# v0.net
KiCad netlist of a schematic drawn in EAGLE
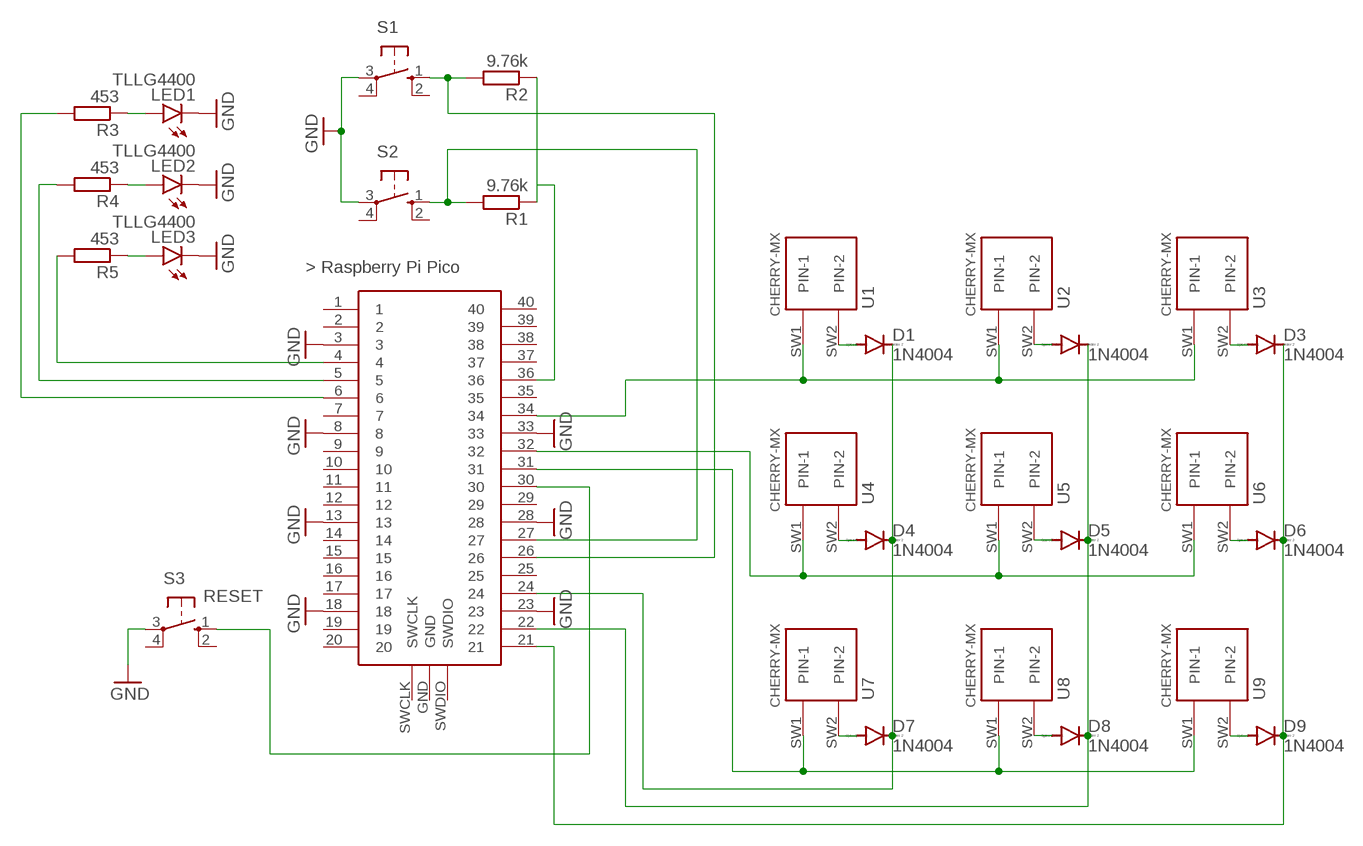
[diagram p0: schematic, sheet 1]

(export (version "E")
  (design (tool "Eeschema 10.0.6"))
  (components
    (comp (ref "D1")
      (value "1N4004")
      (footprint "eagle-import:DO41-10")
      (libsource (lib "eagle-import") (part "1N4004"))
    )
    (comp (ref "D2")
      (value "1N4004")
      (footprint "eagle-import:DO41-10")
      (libsource (lib "eagle-import") (part "1N4004"))
    )
    (comp (ref "D3")
      (value "1N4004")
      (footprint "eagle-import:DO41-10")
      (libsource (lib "eagle-import") (part "1N4004"))
    )
    (comp (ref "D4")
      (value "1N4004")
      (footprint "eagle-import:DO41-10")
      (libsource (lib "eagle-import") (part "1N4004"))
    )
    (comp (ref "D5")
      (value "1N4004")
      (footprint "eagle-import:DO41-10")
      (libsource (lib "eagle-import") (part "1N4004"))
    )
    (comp (ref "D6")
      (value "1N4004")
      (footprint "eagle-import:DO41-10")
      (libsource (lib "eagle-import") (part "1N4004"))
    )
    (comp (ref "D7")
      (value "1N4004")
      (footprint "eagle-import:DO41-10")
      (libsource (lib "eagle-import") (part "1N4004"))
    )
    (comp (ref "D8")
      (value "1N4004")
      (footprint "eagle-import:DO41-10")
      (libsource (lib "eagle-import") (part "1N4004"))
    )
    (comp (ref "D9")
      (value "1N4004")
      (footprint "eagle-import:DO41-10")
      (libsource (lib "eagle-import") (part "1N4004"))
    )
    (comp (ref "LED1")
      (value "TLLG4400")
      (footprint "eagle-import:LED3MM")
      (fields (field (name "MF") "VISHAY SEMICONDUCTOR"))
      (libsource (lib "eagle-import") (part "TLLG4400"))
    )
    (comp (ref "LED2")
      (value "TLLG4400")
      (footprint "eagle-import:LED3MM")
      (fields (field (name "MF") "VISHAY SEMICONDUCTOR"))
      (libsource (lib "eagle-import") (part "TLLG4400"))
    )
    (comp (ref "LED3")
      (value "TLLG4400")
      (footprint "eagle-import:LED3MM")
      (fields (field (name "MF") "VISHAY SEMICONDUCTOR"))
      (libsource (lib "eagle-import") (part "TLLG4400"))
    )
    (comp (ref "R1")
      (value "9.76k")
      (footprint "eagle-import:VMTA55")
      (libsource (lib "eagle-import") (part "R-EU_VMTA55"))
    )
    (comp (ref "R2")
      (value "9.76k")
      (footprint "eagle-import:VMTA55")
      (libsource (lib "eagle-import") (part "R-EU_VMTA55"))
    )
    (comp (ref "R3")
      (value "453")
      (footprint "eagle-import:VMTA55")
      (libsource (lib "eagle-import") (part "R-EU_VMTA55"))
    )
    (comp (ref "R4")
      (value "453")
      (footprint "eagle-import:VMTA55")
      (libsource (lib "eagle-import") (part "R-EU_VMTA55"))
    )
    (comp (ref "R5")
      (value "453")
      (footprint "eagle-import:VMTA55")
      (libsource (lib "eagle-import") (part "R-EU_VMTA55"))
    )
    (comp (ref "S1")
      (value "10-XX")
      (footprint "eagle-import:B3F-10XX")
      (fields (field (name "MPN") "B3F-1000"))
      (libsource (lib "eagle-import") (part "10-XX"))
    )
    (comp (ref "S2")
      (value "10-XX")
      (footprint "eagle-import:B3F-10XX")
      (fields (field (name "MPN") "B3F-1000"))
      (libsource (lib "eagle-import") (part "10-XX"))
    )
    (comp (ref "S3")
      (value "RESET")
      (footprint "eagle-import:B3F-10XX")
      (fields (field (name "MPN") "B3F-1000"))
      (libsource (lib "eagle-import") (part "10-XX"))
    )
    (comp (ref "U$1")
      (value "RASPBERRY-PI-PICO_TH")
      (footprint "eagle-import:FT_RASPBERRY-PI-PICO_TH")
      (libsource (lib "eagle-import") (part "RASPBERRY-PI-PICO_TH"))
    )
    (comp (ref "U1")
      (value "CHERRY-MX")
      (footprint "eagle-import:CHERRY-MX")
      (libsource (lib "eagle-import") (part "CHERRY-MX"))
    )
    (comp (ref "U2")
      (value "CHERRY-MX")
      (footprint "eagle-import:CHERRY-MX")
      (libsource (lib "eagle-import") (part "CHERRY-MX"))
    )
    (comp (ref "U3")
      (value "CHERRY-MX")
      (footprint "eagle-import:CHERRY-MX")
      (libsource (lib "eagle-import") (part "CHERRY-MX"))
    )
    (comp (ref "U4")
      (value "CHERRY-MX")
      (footprint "eagle-import:CHERRY-MX")
      (libsource (lib "eagle-import") (part "CHERRY-MX"))
    )
    (comp (ref "U5")
      (value "CHERRY-MX")
      (footprint "eagle-import:CHERRY-MX")
      (libsource (lib "eagle-import") (part "CHERRY-MX"))
    )
    (comp (ref "U6")
      (value "CHERRY-MX")
      (footprint "eagle-import:CHERRY-MX")
      (libsource (lib "eagle-import") (part "CHERRY-MX"))
    )
    (comp (ref "U7")
      (value "CHERRY-MX")
      (footprint "eagle-import:CHERRY-MX")
      (libsource (lib "eagle-import") (part "CHERRY-MX"))
    )
    (comp (ref "U8")
      (value "CHERRY-MX")
      (footprint "eagle-import:CHERRY-MX")
      (libsource (lib "eagle-import") (part "CHERRY-MX"))
    )
    (comp (ref "U9")
      (value "CHERRY-MX")
      (footprint "eagle-import:CHERRY-MX")
      (libsource (lib "eagle-import") (part "CHERRY-MX"))
    )
  )
  (nets
    (net (code "1") (name "GND") (class "Default")
      (node (ref "LED1") (pin "K") (pinfunction "C_K") (pintype "passive"))
      (node (ref "LED2") (pin "K") (pinfunction "C_K") (pintype "passive"))
      (node (ref "LED3") (pin "K") (pinfunction "C_K") (pintype "passive"))
      (node (ref "S1") (pin "3") (pinfunction "P_3") (pintype "passive"))
      (node (ref "S2") (pin "3") (pinfunction "P_3") (pintype "passive"))
      (node (ref "S3") (pin "3") (pinfunction "P_3") (pintype "passive"))
      (node (ref "U$1") (pin "13") (pinfunction "13_13") (pintype "bidirectional"))
      (node (ref "U$1") (pin "18") (pinfunction "18_18") (pintype "bidirectional"))
      (node (ref "U$1") (pin "23") (pinfunction "23_23") (pintype "bidirectional"))
      (node (ref "U$1") (pin "28") (pinfunction "28_28") (pintype "bidirectional"))
      (node (ref "U$1") (pin "3") (pinfunction "3_3") (pintype "bidirectional"))
      (node (ref "U$1") (pin "33") (pinfunction "33_33") (pintype "bidirectional"))
      (node (ref "U$1") (pin "8") (pinfunction "8_8") (pintype "bidirectional"))
    )
    (net (code "2") (name "Net-(D1-PadC)") (class "Default")
      (node (ref "D1") (pin "C") (pinfunction "C_C") (pintype "passive"))
      (node (ref "D4") (pin "C") (pinfunction "C_C") (pintype "passive"))
      (node (ref "D7") (pin "C") (pinfunction "C_C") (pintype "passive"))
      (node (ref "U$1") (pin "24") (pinfunction "24_24") (pintype "bidirectional"))
    )
    (net (code "3") (name "Net-(D2-PadC)") (class "Default")
      (node (ref "D2") (pin "C") (pinfunction "C_C") (pintype "passive"))
      (node (ref "D5") (pin "C") (pinfunction "C_C") (pintype "passive"))
      (node (ref "D8") (pin "C") (pinfunction "C_C") (pintype "passive"))
      (node (ref "U$1") (pin "22") (pinfunction "22_22") (pintype "bidirectional"))
    )
    (net (code "4") (name "Net-(D3-PadC)") (class "Default")
      (node (ref "D3") (pin "C") (pinfunction "C_C") (pintype "passive"))
      (node (ref "D6") (pin "C") (pinfunction "C_C") (pintype "passive"))
      (node (ref "D9") (pin "C") (pinfunction "C_C") (pintype "passive"))
      (node (ref "U$1") (pin "21") (pinfunction "21_21") (pintype "bidirectional"))
    )
    (net (code "5") (name "Net-(LED1-PadA)") (class "Default")
      (node (ref "LED1") (pin "A") (pinfunction "A_A") (pintype "passive"))
      (node (ref "R3") (pin "1") (pinfunction "1_1") (pintype "passive"))
    )
    (net (code "6") (name "Net-(LED2-PadA)") (class "Default")
      (node (ref "LED2") (pin "A") (pinfunction "A_A") (pintype "passive"))
      (node (ref "R4") (pin "1") (pinfunction "1_1") (pintype "passive"))
    )
    (net (code "7") (name "Net-(LED3-PadA)") (class "Default")
      (node (ref "LED3") (pin "A") (pinfunction "A_A") (pintype "passive"))
      (node (ref "R5") (pin "1") (pinfunction "1_1") (pintype "passive"))
    )
    (net (code "8") (name "Net-(R1-Pad1)") (class "Default")
      (node (ref "R1") (pin "1") (pinfunction "1_1") (pintype "passive"))
      (node (ref "R2") (pin "1") (pinfunction "1_1") (pintype "passive"))
      (node (ref "U$1") (pin "36") (pinfunction "36_36") (pintype "bidirectional"))
    )
    (net (code "9") (name "Net-(R3-Pad2)") (class "Default")
      (node (ref "R3") (pin "2") (pinfunction "2_2") (pintype "passive"))
      (node (ref "U$1") (pin "6") (pinfunction "6_6") (pintype "bidirectional"))
    )
    (net (code "10") (name "Net-(R4-Pad2)") (class "Default")
      (node (ref "R4") (pin "2") (pinfunction "2_2") (pintype "passive"))
      (node (ref "U$1") (pin "5") (pinfunction "5_5") (pintype "bidirectional"))
    )
    (net (code "11") (name "Net-(R5-Pad2)") (class "Default")
      (node (ref "R5") (pin "2") (pinfunction "2_2") (pintype "passive"))
      (node (ref "U$1") (pin "4") (pinfunction "4_4") (pintype "bidirectional"))
    )
    (net (code "12") (name "Net-(S1-S)") (class "Default")
      (node (ref "R2") (pin "2") (pinfunction "2_2") (pintype "passive"))
      (node (ref "S1") (pin "1") (pinfunction "S_1") (pintype "passive"))
      (node (ref "U$1") (pin "26") (pinfunction "26_26") (pintype "bidirectional"))
    )
    (net (code "13") (name "Net-(S2-S)") (class "Default")
      (node (ref "R1") (pin "2") (pinfunction "2_2") (pintype "passive"))
      (node (ref "S2") (pin "1") (pinfunction "S_1") (pintype "passive"))
      (node (ref "U$1") (pin "27") (pinfunction "27_27") (pintype "bidirectional"))
    )
    (net (code "14") (name "Net-(S3-S)") (class "Default")
      (node (ref "S3") (pin "1") (pinfunction "S_1") (pintype "passive"))
      (node (ref "U$1") (pin "30") (pinfunction "30_30") (pintype "bidirectional"))
    )
    (net (code "15") (name "Net-(U1-PIN-1)") (class "Default")
      (node (ref "U$1") (pin "34") (pinfunction "34_34") (pintype "bidirectional"))
      (node (ref "U1") (pin "SW1") (pinfunction "PIN-1_SW1") (pintype "bidirectional"))
      (node (ref "U2") (pin "SW1") (pinfunction "PIN-1_SW1") (pintype "bidirectional"))
      (node (ref "U3") (pin "SW1") (pinfunction "PIN-1_SW1") (pintype "bidirectional"))
    )
    (net (code "16") (name "Net-(U1-PIN-2)") (class "Default")
      (node (ref "D1") (pin "A") (pinfunction "A_A") (pintype "passive"))
      (node (ref "U1") (pin "SW2") (pinfunction "PIN-2_SW2") (pintype "bidirectional"))
    )
    (net (code "17") (name "Net-(U2-PIN-2)") (class "Default")
      (node (ref "D2") (pin "A") (pinfunction "A_A") (pintype "passive"))
      (node (ref "U2") (pin "SW2") (pinfunction "PIN-2_SW2") (pintype "bidirectional"))
    )
    (net (code "18") (name "Net-(U3-PIN-2)") (class "Default")
      (node (ref "D3") (pin "A") (pinfunction "A_A") (pintype "passive"))
      (node (ref "U3") (pin "SW2") (pinfunction "PIN-2_SW2") (pintype "bidirectional"))
    )
    (net (code "19") (name "Net-(U4-PIN-1)") (class "Default")
      (node (ref "U$1") (pin "32") (pinfunction "32_32") (pintype "bidirectional"))
      (node (ref "U4") (pin "SW1") (pinfunction "PIN-1_SW1") (pintype "bidirectional"))
      (node (ref "U5") (pin "SW1") (pinfunction "PIN-1_SW1") (pintype "bidirectional"))
      (node (ref "U6") (pin "SW1") (pinfunction "PIN-1_SW1") (pintype "bidirectional"))
    )
    (net (code "20") (name "Net-(U4-PIN-2)") (class "Default")
      (node (ref "D4") (pin "A") (pinfunction "A_A") (pintype "passive"))
      (node (ref "U4") (pin "SW2") (pinfunction "PIN-2_SW2") (pintype "bidirectional"))
    )
    (net (code "21") (name "Net-(U5-PIN-2)") (class "Default")
      (node (ref "D5") (pin "A") (pinfunction "A_A") (pintype "passive"))
      (node (ref "U5") (pin "SW2") (pinfunction "PIN-2_SW2") (pintype "bidirectional"))
    )
    (net (code "22") (name "Net-(U6-PIN-2)") (class "Default")
      (node (ref "D6") (pin "A") (pinfunction "A_A") (pintype "passive"))
      (node (ref "U6") (pin "SW2") (pinfunction "PIN-2_SW2") (pintype "bidirectional"))
    )
    (net (code "23") (name "Net-(U7-PIN-1)") (class "Default")
      (node (ref "U$1") (pin "31") (pinfunction "31_31") (pintype "bidirectional"))
      (node (ref "U7") (pin "SW1") (pinfunction "PIN-1_SW1") (pintype "bidirectional"))
      (node (ref "U8") (pin "SW1") (pinfunction "PIN-1_SW1") (pintype "bidirectional"))
      (node (ref "U9") (pin "SW1") (pinfunction "PIN-1_SW1") (pintype "bidirectional"))
    )
    (net (code "24") (name "Net-(U7-PIN-2)") (class "Default")
      (node (ref "D7") (pin "A") (pinfunction "A_A") (pintype "passive"))
      (node (ref "U7") (pin "SW2") (pinfunction "PIN-2_SW2") (pintype "bidirectional"))
    )
    (net (code "25") (name "Net-(U8-PIN-2)") (class "Default")
      (node (ref "D8") (pin "A") (pinfunction "A_A") (pintype "passive"))
      (node (ref "U8") (pin "SW2") (pinfunction "PIN-2_SW2") (pintype "bidirectional"))
    )
    (net (code "26") (name "Net-(U9-PIN-2)") (class "Default")
      (node (ref "D9") (pin "A") (pinfunction "A_A") (pintype "passive"))
      (node (ref "U9") (pin "SW2") (pinfunction "PIN-2_SW2") (pintype "bidirectional"))
    )
    (net (code "27") (name "unconnected-(S1-P1-Pad4)") (class "Default")
      (node (ref "S1") (pin "4") (pinfunction "P1_4") (pintype "passive"))
    )
    (net (code "28") (name "unconnected-(S1-S1-Pad2)") (class "Default")
      (node (ref "S1") (pin "2") (pinfunction "S1_2") (pintype "passive"))
    )
    (net (code "29") (name "unconnected-(S2-P1-Pad4)") (class "Default")
      (node (ref "S2") (pin "4") (pinfunction "P1_4") (pintype "passive"))
    )
    (net (code "30") (name "unconnected-(S2-S1-Pad2)") (class "Default")
      (node (ref "S2") (pin "2") (pinfunction "S1_2") (pintype "passive"))
    )
    (net (code "31") (name "unconnected-(S3-P1-Pad4)") (class "Default")
      (node (ref "S3") (pin "4") (pinfunction "P1_4") (pintype "passive"))
    )
    (net (code "32") (name "unconnected-(S3-S1-Pad2)") (class "Default")
      (node (ref "S3") (pin "2") (pinfunction "S1_2") (pintype "passive"))
    )
    (net (code "33") (name "unconnected-(U$1-Pad1)") (class "Default")
      (node (ref "U$1") (pin "1") (pinfunction "1_1") (pintype "bidirectional"))
    )
    (net (code "34") (name "unconnected-(U$1-Pad2)") (class "Default")
      (node (ref "U$1") (pin "2") (pinfunction "2_2") (pintype "bidirectional"))
    )
    (net (code "35") (name "unconnected-(U$1-Pad7)") (class "Default")
      (node (ref "U$1") (pin "7") (pinfunction "7_7") (pintype "bidirectional"))
    )
    (net (code "36") (name "unconnected-(U$1-Pad9)") (class "Default")
      (node (ref "U$1") (pin "9") (pinfunction "9_9") (pintype "bidirectional"))
    )
    (net (code "37") (name "unconnected-(U$1-Pad10)") (class "Default")
      (node (ref "U$1") (pin "10") (pinfunction "10_10") (pintype "bidirectional"))
    )
    (net (code "38") (name "unconnected-(U$1-Pad11)") (class "Default")
      (node (ref "U$1") (pin "11") (pinfunction "11_11") (pintype "bidirectional"))
    )
    (net (code "39") (name "unconnected-(U$1-Pad12)") (class "Default")
      (node (ref "U$1") (pin "12") (pinfunction "12_12") (pintype "bidirectional"))
    )
    (net (code "40") (name "unconnected-(U$1-Pad14)") (class "Default")
      (node (ref "U$1") (pin "14") (pinfunction "14_14") (pintype "bidirectional"))
    )
    (net (code "41") (name "unconnected-(U$1-Pad15)") (class "Default")
      (node (ref "U$1") (pin "15") (pinfunction "15_15") (pintype "bidirectional"))
    )
    (net (code "42") (name "unconnected-(U$1-Pad16)") (class "Default")
      (node (ref "U$1") (pin "16") (pinfunction "16_16") (pintype "bidirectional"))
    )
    (net (code "43") (name "unconnected-(U$1-Pad17)") (class "Default")
      (node (ref "U$1") (pin "17") (pinfunction "17_17") (pintype "bidirectional"))
    )
    (net (code "44") (name "unconnected-(U$1-Pad19)") (class "Default")
      (node (ref "U$1") (pin "19") (pinfunction "19_19") (pintype "bidirectional"))
    )
    (net (code "45") (name "unconnected-(U$1-Pad20)") (class "Default")
      (node (ref "U$1") (pin "20") (pinfunction "20_20") (pintype "bidirectional"))
    )
    (net (code "46") (name "unconnected-(U$1-Pad25)") (class "Default")
      (node (ref "U$1") (pin "25") (pinfunction "25_25") (pintype "bidirectional"))
    )
    (net (code "47") (name "unconnected-(U$1-Pad29)") (class "Default")
      (node (ref "U$1") (pin "29") (pinfunction "29_29") (pintype "bidirectional"))
    )
    (net (code "48") (name "unconnected-(U$1-Pad35)") (class "Default")
      (node (ref "U$1") (pin "35") (pinfunction "35_35") (pintype "bidirectional"))
    )
    (net (code "49") (name "unconnected-(U$1-Pad37)") (class "Default")
      (node (ref "U$1") (pin "37") (pinfunction "37_37") (pintype "bidirectional"))
    )
    (net (code "50") (name "unconnected-(U$1-Pad38)") (class "Default")
      (node (ref "U$1") (pin "38") (pinfunction "38_38") (pintype "bidirectional"))
    )
    (net (code "51") (name "unconnected-(U$1-Pad39)") (class "Default")
      (node (ref "U$1") (pin "39") (pinfunction "39_39") (pintype "bidirectional"))
    )
    (net (code "52") (name "unconnected-(U$1-Pad40)") (class "Default")
      (node (ref "U$1") (pin "40") (pinfunction "40_40") (pintype "bidirectional"))
    )
    (net (code "53") (name "unconnected-(U$1-PadGND)") (class "Default")
      (node (ref "U$1") (pin "GND") (pinfunction "GND_GND") (pintype "bidirectional"))
    )
    (net (code "54") (name "unconnected-(U$1-PadSWCLK)") (class "Default")
      (node (ref "U$1") (pin "SWCLK") (pinfunction "SWCLK_SWCLK") (pintype "bidirectional"))
    )
    (net (code "55") (name "unconnected-(U$1-PadSWDIO)") (class "Default")
      (node (ref "U$1") (pin "SWDIO") (pinfunction "SWDIO_SWDIO") (pintype "bidirectional"))
    )
  )
)
